# sls_v1_0.net
KiCad netlist of a schematic drawn in EAGLE
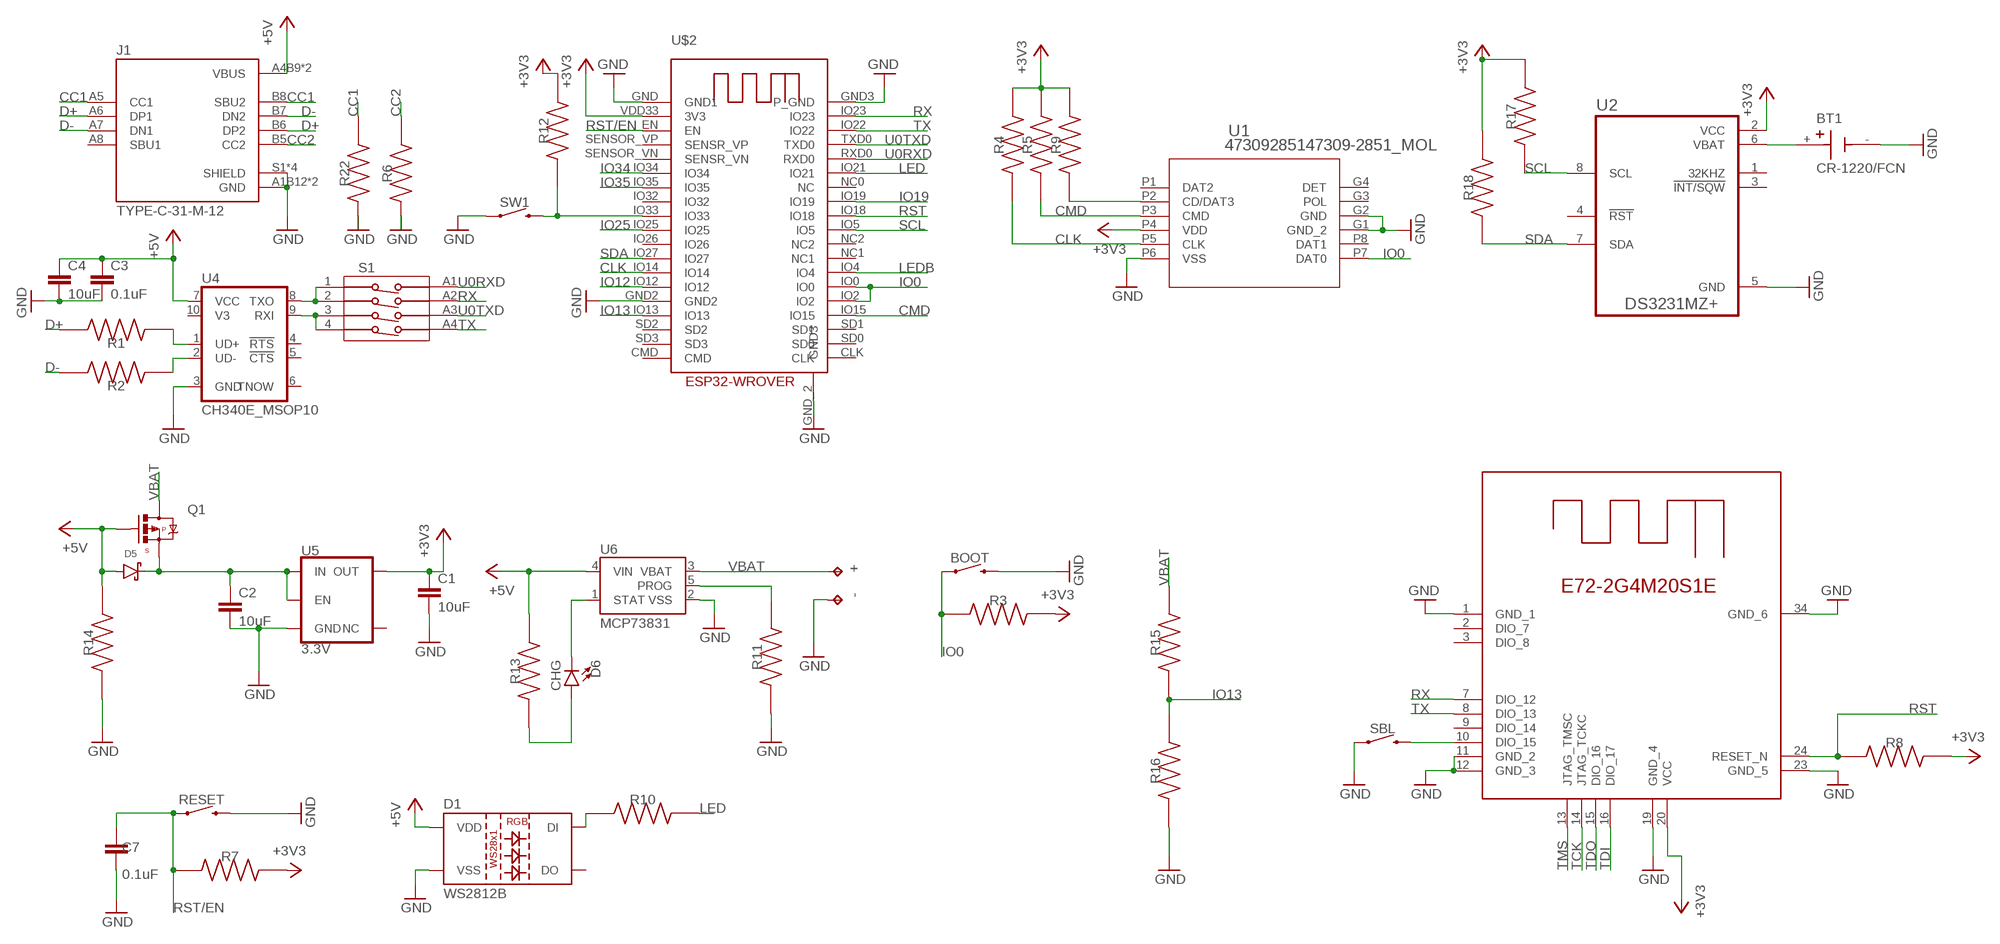
[diagram p0: schematic, sheet 1]

(export (version "E")
  (design (tool "Eeschema 10.0.6"))
  (components
    (comp (ref "+")
      (value "TPTP14R")
      (footprint "eagle-import:TP14R")
      (libsource (lib "eagle-import") (part "TPTP14R"))
    )
    (comp (ref "-")
      (value "TPTP14R")
      (footprint "eagle-import:TP14R")
      (libsource (lib "eagle-import") (part "TPTP14R"))
    )
    (comp (ref "BOOT")
      (value "MOMENTARY-SWITCH-SPST-SMD-4.6X2.8MM")
      (footprint "eagle-import:TACTILE_SWITCH_SMD_4.6X2.8MM")
      (libsource (lib "eagle-import") (part "MOMENTARY-SWITCH-SPST-SMD-4.6X2.8MM"))
    )
    (comp (ref "BT1")
      (value "CR-1220/FCN")
      (footprint "eagle-import:BAT_CR-1220_FCN")
      (fields (field (name "MF") "Panasonic -"))
      (libsource (lib "eagle-import") (part "CR-1220/FCN"))
    )
    (comp (ref "C1")
      (value "10uF")
      (footprint "eagle-import:0805")
      (libsource (lib "eagle-import") (part "10UF-0805-10V-10%"))
    )
    (comp (ref "C2")
      (value "10uF")
      (footprint "eagle-import:0805")
      (libsource (lib "eagle-import") (part "10UF-0805-10V-10%"))
    )
    (comp (ref "C3")
      (value "0.1uF")
      (footprint "eagle-import:0603")
      (libsource (lib "eagle-import") (part "0.1UF-0603-25V-(+80/-20%)"))
    )
    (comp (ref "C4")
      (value "10uF")
      (footprint "eagle-import:0603")
      (libsource (lib "eagle-import") (part "10UF-0603-6.3V-20%"))
    )
    (comp (ref "C7")
      (value "0.1uF")
      (footprint "eagle-import:0603")
      (libsource (lib "eagle-import") (part "0.1UF-0603-25V-5%"))
    )
    (comp (ref "D1")
      (value "WS2812B")
      (footprint "eagle-import:WS2812B")
      (libsource (lib "eagle-import") (part "WS2812B"))
    )
    (comp (ref "D5")
      (value "DIODE-SCHOTTKY")
      (footprint "eagle-import:SOD-323")
      (libsource (lib "eagle-import") (part "DIODE-SCHOTTKY"))
    )
    (comp (ref "D6")
      (value "CHG")
      (footprint "eagle-import:LED-0603")
      (libsource (lib "eagle-import") (part "LED-BLUE0603"))
    )
    (comp (ref "J1")
      (value "TYPE-C-31-M-12")
      (footprint "eagle-import:HRO_TYPE-C-31-M-12")
      (fields (field (name "MF") "HRO Electronics Co., Ltd."))
      (libsource (lib "eagle-import") (part "TYPE-C-31-M-12"))
    )
    (comp (ref "Q1")
      (value "MOSFET-PCHANNEL")
      (footprint "eagle-import:SOT23")
      (libsource (lib "eagle-import") (part "MOSFET-PCHANNEL"))
    )
    (comp (ref "R1")
      (value "RC0402FR-073M6L")
      (footprint "eagle-import:RESC1005X40N")
      (fields (field (name "MF") "Yageo"))
      (libsource (lib "eagle-import") (part "RC0402FR-073M6L"))
    )
    (comp (ref "R2")
      (value "RC0402FR-073M6L")
      (footprint "eagle-import:RESC1005X40N")
      (fields (field (name "MF") "Yageo"))
      (libsource (lib "eagle-import") (part "RC0402FR-073M6L"))
    )
    (comp (ref "R3")
      (value "RC0402FR-073M6L")
      (footprint "eagle-import:RESC1005X40N")
      (fields (field (name "MF") "Yageo"))
      (libsource (lib "eagle-import") (part "RC0402FR-073M6L"))
    )
    (comp (ref "R4")
      (value "RC0402FR-073M6L")
      (footprint "eagle-import:RESC1005X40N")
      (fields (field (name "MF") "Yageo"))
      (libsource (lib "eagle-import") (part "RC0402FR-073M6L"))
    )
    (comp (ref "R5")
      (value "RC0402FR-073M6L")
      (footprint "eagle-import:RESC1005X40N")
      (fields (field (name "MF") "Yageo"))
      (libsource (lib "eagle-import") (part "RC0402FR-073M6L"))
    )
    (comp (ref "R6")
      (value "5.1k")
      (footprint "eagle-import:RESC1005X40N")
      (fields (field (name "MF") "Yageo") (field (name "MP") "RC0402FR-073M6L"))
      (libsource (lib "eagle-import") (part "RC0402FR-073M6L"))
    )
    (comp (ref "R7")
      (value "RC0402FR-073M6L")
      (footprint "eagle-import:RESC1005X40N")
      (fields (field (name "MF") "Yageo"))
      (libsource (lib "eagle-import") (part "RC0402FR-073M6L"))
    )
    (comp (ref "R8")
      (value "100k")
      (footprint "eagle-import:RESC1005X40N")
      (fields (field (name "MF") "Yageo") (field (name "MP") "RC0402FR-073M6L"))
      (libsource (lib "eagle-import") (part "RC0402FR-073M6L"))
    )
    (comp (ref "R9")
      (value "RC0402FR-073M6L")
      (footprint "eagle-import:RESC1005X40N")
      (fields (field (name "MF") "Yageo"))
      (libsource (lib "eagle-import") (part "RC0402FR-073M6L"))
    )
    (comp (ref "R10")
      (value "RC0402FR-073M6L")
      (footprint "eagle-import:RESC1005X40N")
      (fields (field (name "MF") "Yageo"))
      (libsource (lib "eagle-import") (part "RC0402FR-073M6L"))
    )
    (comp (ref "R11")
      (value "2.7k")
      (footprint "eagle-import:RESC1005X40N")
      (fields (field (name "MF") "Yageo") (field (name "MP") "RC0402FR-073M6L"))
      (libsource (lib "eagle-import") (part "RC0402FR-073M6L"))
    )
    (comp (ref "R12")
      (value "RC0402FR-073M6L")
      (footprint "eagle-import:RESC1005X40N")
      (fields (field (name "MF") "Yageo"))
      (libsource (lib "eagle-import") (part "RC0402FR-073M6L"))
    )
    (comp (ref "R13")
      (value "RC0402FR-073M6L")
      (footprint "eagle-import:RESC1005X40N")
      (fields (field (name "MF") "Yageo"))
      (libsource (lib "eagle-import") (part "RC0402FR-073M6L"))
    )
    (comp (ref "R14")
      (value "RC0402FR-073M6L")
      (footprint "eagle-import:RESC1005X40N")
      (fields (field (name "MF") "Yageo"))
      (libsource (lib "eagle-import") (part "RC0402FR-073M6L"))
    )
    (comp (ref "R15")
      (value "RC0402FR-073M6L")
      (footprint "eagle-import:RESC1005X40N")
      (fields (field (name "MF") "Yageo"))
      (libsource (lib "eagle-import") (part "RC0402FR-073M6L"))
    )
    (comp (ref "R16")
      (value "RC0402FR-073M6L")
      (footprint "eagle-import:RESC1005X40N")
      (fields (field (name "MF") "Yageo"))
      (libsource (lib "eagle-import") (part "RC0402FR-073M6L"))
    )
    (comp (ref "R17")
      (value "RC0402FR-073M6L")
      (footprint "eagle-import:RESC1005X40N")
      (fields (field (name "MF") "Yageo"))
      (libsource (lib "eagle-import") (part "RC0402FR-073M6L"))
    )
    (comp (ref "R18")
      (value "RC0402FR-073M6L")
      (footprint "eagle-import:RESC1005X40N")
      (fields (field (name "MF") "Yageo"))
      (libsource (lib "eagle-import") (part "RC0402FR-073M6L"))
    )
    (comp (ref "R22")
      (value "5.1k")
      (footprint "eagle-import:RESC1005X40N")
      (fields (field (name "MF") "Yageo") (field (name "MP") "RC0402FR-073M6L"))
      (libsource (lib "eagle-import") (part "RC0402FR-073M6L"))
    )
    (comp (ref "RESET")
      (value "MOMENTARY-SWITCH-SPST-SMD-4.6X2.8MM")
      (footprint "eagle-import:TACTILE_SWITCH_SMD_4.6X2.8MM")
      (libsource (lib "eagle-import") (part "MOMENTARY-SWITCH-SPST-SMD-4.6X2.8MM"))
    )
    (comp (ref "S1")
      (value "416131160804")
      (footprint "eagle-import:416131160804")
      (fields (field (name "MF") "Wurth Elektronik"))
      (libsource (lib "eagle-import") (part "416131160804"))
    )
    (comp (ref "SBL")
      (value "MOMENTARY-SWITCH-SPST-SMD-4.6X2.8MM")
      (footprint "eagle-import:TACTILE_SWITCH_SMD_4.6X2.8MM")
      (libsource (lib "eagle-import") (part "MOMENTARY-SWITCH-SPST-SMD-4.6X2.8MM"))
    )
    (comp (ref "SW1")
      (value "MOMENTARY-SWITCH-SPST-SMD-4.6X2.8MM")
      (footprint "eagle-import:TACTILE_SWITCH_SMD_4.6X2.8MM")
      (libsource (lib "eagle-import") (part "MOMENTARY-SWITCH-SPST-SMD-4.6X2.8MM"))
    )
    (comp (ref "U$1")
      (value "E72-2G4M20S1E")
      (footprint "eagle-import:E72-2G4M20S1E")
      (libsource (lib "eagle-import") (part "E72-2G4M20S1E"))
    )
    (comp (ref "U$2")
      (value "ESP32-WROVER")
      (footprint "eagle-import:ESP32-WROVER")
      (libsource (lib "eagle-import") (part "ESP32-WROVER"))
    )
    (comp (ref "U1")
      (value "47309285147309-2851_MOL")
      (footprint "eagle-import:47309-2851_MOL")
      (fields
        (field (name "MANUFACTURER_PART_NUMBER") "473092851")
        (field (name "COPYRIGHT") "Copyright (C) 2021 Ultra Librarian. All rights reserved.")
      )
      (libsource (lib "eagle-import") (part "47309285147309-2851_MOL"))
    )
    (comp (ref "U2")
      (value "DS3231MZ+")
      (footprint "eagle-import:SOIC127P600X175-8N")
      (fields (field (name "MF") "Maxim Integrated"))
      (libsource (lib "eagle-import") (part "DS3231MZ+"))
    )
    (comp (ref "U4")
      (value "CH340E_MSOP10")
      (footprint "eagle-import:MSOP10")
      (fields (field (name "MF") "WCH") (field (name "MP") "CH340E"))
      (libsource (lib "eagle-import") (part "CH340E_MSOP10"))
    )
    (comp (ref "U5")
      (value "3.3V")
      (footprint "eagle-import:SOT23-5")
      (libsource (lib "eagle-import") (part "V_REG_AP2112K-3.3V"))
    )
    (comp (ref "U6")
      (value "MCP73831")
      (footprint "eagle-import:SOT23-5")
      (libsource (lib "eagle-import") (part "MCP73831"))
    )
  )
  (nets
    (net (code "1") (name "+3V3") (class "Default")
      (node (ref "C1") (pin "1") (pinfunction "1_1") (pintype "passive"))
      (node (ref "R12") (pin "2") (pinfunction "2_2") (pintype "passive"))
      (node (ref "R17") (pin "2") (pinfunction "2_2") (pintype "passive"))
      (node (ref "R18") (pin "2") (pinfunction "2_2") (pintype "passive"))
      (node (ref "R3") (pin "2") (pinfunction "2_2") (pintype "passive"))
      (node (ref "R4") (pin "2") (pinfunction "2_2") (pintype "passive"))
      (node (ref "R5") (pin "2") (pinfunction "2_2") (pintype "passive"))
      (node (ref "R7") (pin "2") (pinfunction "2_2") (pintype "passive"))
      (node (ref "R8") (pin "2") (pinfunction "2_2") (pintype "passive"))
      (node (ref "R9") (pin "2") (pinfunction "2_2") (pintype "passive"))
      (node (ref "U$1") (pin "20") (pinfunction "VCC_20") (pintype "bidirectional"))
      (node (ref "U$2") (pin "VDD33") (pinfunction "3V3_VDD33") (pintype "bidirectional"))
      (node (ref "U1") (pin "P4") (pinfunction "VDD_P4") (pintype "power_in"))
      (node (ref "U2") (pin "2") (pinfunction "VCC_2") (pintype "power_in"))
      (node (ref "U5") (pin "5") (pinfunction "OUT_5") (pintype "passive"))
    )
    (net (code "2") (name "+5V") (class "Default")
      (node (ref "C3") (pin "1") (pinfunction "1_1") (pintype "passive"))
      (node (ref "C4") (pin "1") (pinfunction "1_1") (pintype "passive"))
      (node (ref "D1") (pin "1") (pinfunction "VDD_1") (pintype "bidirectional"))
      (node (ref "D5") (pin "A") (pinfunction "A_A") (pintype "passive"))
      (node (ref "J1") (pin "A4B9") (pinfunction "VBUS_A4B9") (pintype "power_in"))
      (node (ref "J1") (pin "B4A9") (pinfunction "VBUS_B4A9") (pintype "power_in"))
      (node (ref "Q1") (pin "1") (pinfunction "G_1") (pintype "passive"))
      (node (ref "R13") (pin "2") (pinfunction "2_2") (pintype "passive"))
      (node (ref "R14") (pin "2") (pinfunction "2_2") (pintype "passive"))
      (node (ref "U4") (pin "7") (pinfunction "VCC_7") (pintype "bidirectional"))
      (node (ref "U6") (pin "4") (pinfunction "VIN_4") (pintype "power_in"))
    )
    (net (code "3") (name "/CC1") (class "Default")
      (node (ref "J1") (pin "A5") (pinfunction "CC1_A5") (pintype "bidirectional"))
      (node (ref "J1") (pin "B8") (pinfunction "SBU2_B8") (pintype "bidirectional"))
      (node (ref "R22") (pin "2") (pinfunction "2_2") (pintype "passive"))
    )
    (net (code "4") (name "/CC2") (class "Default")
      (node (ref "J1") (pin "B5") (pinfunction "CC2_B5") (pintype "bidirectional"))
      (node (ref "R6") (pin "2") (pinfunction "2_2") (pintype "passive"))
    )
    (net (code "5") (name "/CLK") (class "Default")
      (node (ref "R4") (pin "1") (pinfunction "1_1") (pintype "passive"))
      (node (ref "U$2") (pin "IO14") (pinfunction "IO14_IO14") (pintype "bidirectional"))
      (node (ref "U1") (pin "P5") (pinfunction "CLK_P5") (pintype "passive"))
    )
    (net (code "6") (name "/CMD") (class "Default")
      (node (ref "R5") (pin "1") (pinfunction "1_1") (pintype "passive"))
      (node (ref "U$2") (pin "IO15") (pinfunction "IO15_IO15") (pintype "bidirectional"))
      (node (ref "U1") (pin "P3") (pinfunction "CMD_P3") (pintype "passive"))
    )
    (net (code "7") (name "/D+") (class "Default")
      (node (ref "J1") (pin "A6") (pinfunction "DP1_A6") (pintype "bidirectional"))
      (node (ref "J1") (pin "B6") (pinfunction "DP2_B6") (pintype "bidirectional"))
      (node (ref "R1") (pin "2") (pinfunction "2_2") (pintype "passive"))
    )
    (net (code "8") (name "/D-") (class "Default")
      (node (ref "J1") (pin "A7") (pinfunction "DN1_A7") (pintype "bidirectional"))
      (node (ref "J1") (pin "B7") (pinfunction "DN2_B7") (pintype "bidirectional"))
      (node (ref "R2") (pin "2") (pinfunction "2_2") (pintype "passive"))
    )
    (net (code "9") (name "/IO0") (class "Default")
      (node (ref "BOOT") (pin "1") (pinfunction "1_1") (pintype "passive"))
      (node (ref "BOOT") (pin "2") (pinfunction "1_2") (pintype "passive"))
      (node (ref "R3") (pin "1") (pinfunction "1_1") (pintype "passive"))
      (node (ref "U$2") (pin "IO0") (pinfunction "IO0_IO0") (pintype "bidirectional"))
      (node (ref "U$2") (pin "IO2") (pinfunction "IO2_IO2") (pintype "bidirectional"))
      (node (ref "U1") (pin "P7") (pinfunction "DAT0_P7") (pintype "bidirectional"))
    )
    (net (code "10") (name "/IO12") (class "Default")
      (node (ref "U$2") (pin "IO12") (pinfunction "IO12_IO12") (pintype "bidirectional"))
    )
    (net (code "11") (name "/IO13") (class "Default")
      (node (ref "R15") (pin "1") (pinfunction "1_1") (pintype "passive"))
      (node (ref "R16") (pin "2") (pinfunction "2_2") (pintype "passive"))
      (node (ref "U$2") (pin "IO13") (pinfunction "IO13_IO13") (pintype "bidirectional"))
    )
    (net (code "12") (name "/IO19") (class "Default")
      (node (ref "U$2") (pin "IO19") (pinfunction "IO19_IO19") (pintype "bidirectional"))
    )
    (net (code "13") (name "/IO25") (class "Default")
      (node (ref "U$2") (pin "IO25") (pinfunction "IO25_IO25") (pintype "bidirectional"))
    )
    (net (code "14") (name "/IO34") (class "Default")
      (node (ref "U$2") (pin "IO34") (pinfunction "IO34_IO34") (pintype "bidirectional"))
    )
    (net (code "15") (name "/IO35") (class "Default")
      (node (ref "U$2") (pin "IO35") (pinfunction "IO35_IO35") (pintype "bidirectional"))
    )
    (net (code "16") (name "/LED") (class "Default")
      (node (ref "R10") (pin "2") (pinfunction "2_2") (pintype "passive"))
      (node (ref "U$2") (pin "IO21") (pinfunction "IO21_IO21") (pintype "bidirectional"))
    )
    (net (code "17") (name "/LEDB") (class "Default")
      (node (ref "U$2") (pin "IO4") (pinfunction "IO4_IO4") (pintype "bidirectional"))
    )
    (net (code "18") (name "/RST") (class "Default")
      (node (ref "R8") (pin "1") (pinfunction "1_1") (pintype "passive"))
      (node (ref "U$1") (pin "24") (pinfunction "RESET_N_24") (pintype "bidirectional"))
      (node (ref "U$2") (pin "IO18") (pinfunction "IO18_IO18") (pintype "bidirectional"))
    )
    (net (code "19") (name "/RST{slash}EN") (class "Default")
      (node (ref "C7") (pin "1") (pinfunction "1_1") (pintype "passive"))
      (node (ref "R7") (pin "1") (pinfunction "1_1") (pintype "passive"))
      (node (ref "RESET") (pin "1") (pinfunction "1_1") (pintype "passive"))
      (node (ref "RESET") (pin "2") (pinfunction "1_2") (pintype "passive"))
      (node (ref "U$2") (pin "EN") (pinfunction "EN_EN") (pintype "bidirectional"))
    )
    (net (code "20") (name "/RX") (class "Default")
      (node (ref "S1") (pin "A2") (pinfunction "A2_A2") (pintype "passive"))
      (node (ref "U$1") (pin "7") (pinfunction "DIO_12_7") (pintype "bidirectional"))
      (node (ref "U$2") (pin "IO23") (pinfunction "IO23_IO23") (pintype "bidirectional"))
    )
    (net (code "21") (name "/SCL") (class "Default")
      (node (ref "R17") (pin "1") (pinfunction "1_1") (pintype "passive"))
      (node (ref "U$2") (pin "IO5") (pinfunction "IO5_IO5") (pintype "bidirectional"))
      (node (ref "U2") (pin "8") (pinfunction "SCL_8") (pintype "input"))
    )
    (net (code "22") (name "/SDA") (class "Default")
      (node (ref "R18") (pin "1") (pinfunction "1_1") (pintype "passive"))
      (node (ref "U$2") (pin "IO27") (pinfunction "IO27_IO27") (pintype "bidirectional"))
      (node (ref "U2") (pin "7") (pinfunction "SDA_7") (pintype "bidirectional"))
    )
    (net (code "23") (name "/TCK") (class "Default")
      (node (ref "U$1") (pin "14") (pinfunction "JTAG_TCKC_14") (pintype "bidirectional"))
    )
    (net (code "24") (name "/TDI") (class "Default")
      (node (ref "U$1") (pin "16") (pinfunction "DIO_17_16") (pintype "bidirectional"))
    )
    (net (code "25") (name "/TDO") (class "Default")
      (node (ref "U$1") (pin "15") (pinfunction "DIO_16_15") (pintype "bidirectional"))
    )
    (net (code "26") (name "/TMS") (class "Default")
      (node (ref "U$1") (pin "13") (pinfunction "JTAG_TMSC_13") (pintype "bidirectional"))
    )
    (net (code "27") (name "/TX") (class "Default")
      (node (ref "S1") (pin "A4") (pinfunction "A4_A4") (pintype "passive"))
      (node (ref "U$1") (pin "8") (pinfunction "DIO_13_8") (pintype "bidirectional"))
      (node (ref "U$2") (pin "IO22") (pinfunction "IO22_IO22") (pintype "bidirectional"))
    )
    (net (code "28") (name "/U0RXD") (class "Default")
      (node (ref "S1") (pin "A1") (pinfunction "A1_A1") (pintype "passive"))
      (node (ref "U$2") (pin "RXD0") (pinfunction "RXD0_RXD0") (pintype "bidirectional"))
    )
    (net (code "29") (name "/U0TXD") (class "Default")
      (node (ref "S1") (pin "A3") (pinfunction "A3_A3") (pintype "passive"))
      (node (ref "U$2") (pin "TXD0") (pinfunction "TXD0_TXD0") (pintype "bidirectional"))
    )
    (net (code "30") (name "/VBAT") (class "Default")
      (node (ref "+") (pin "TP") (pinfunction "TP_TP") (pintype "input"))
      (node (ref "Q1") (pin "3") (pinfunction "D_3") (pintype "passive"))
      (node (ref "R15") (pin "2") (pinfunction "2_2") (pintype "passive"))
      (node (ref "U6") (pin "3") (pinfunction "VBAT_3") (pintype "power_in"))
    )
    (net (code "31") (name "GND") (class "Default")
      (node (ref "-") (pin "TP") (pinfunction "TP_TP") (pintype "input"))
      (node (ref "BOOT") (pin "3") (pinfunction "2_3") (pintype "passive"))
      (node (ref "BOOT") (pin "4") (pinfunction "2_4") (pintype "passive"))
      (node (ref "BT1") (pin "-") (pinfunction "-_-") (pintype "passive"))
      (node (ref "C1") (pin "2") (pinfunction "2_2") (pintype "passive"))
      (node (ref "C2") (pin "2") (pinfunction "2_2") (pintype "passive"))
      (node (ref "C3") (pin "2") (pinfunction "2_2") (pintype "passive"))
      (node (ref "C4") (pin "2") (pinfunction "2_2") (pintype "passive"))
      (node (ref "C7") (pin "2") (pinfunction "2_2") (pintype "passive"))
      (node (ref "D1") (pin "3") (pinfunction "VSS_3") (pintype "bidirectional"))
      (node (ref "J1") (pin "A1B12") (pinfunction "GND_A1B12") (pintype "power_in"))
      (node (ref "J1") (pin "B1A12") (pinfunction "GND_B1A12") (pintype "power_in"))
      (node (ref "J1") (pin "S1") (pinfunction "SHIELD_S1") (pintype "passive"))
      (node (ref "J1") (pin "S2") (pinfunction "SHIELD_S2") (pintype "passive"))
      (node (ref "J1") (pin "S3") (pinfunction "SHIELD_S3") (pintype "passive"))
      (node (ref "J1") (pin "S4") (pinfunction "SHIELD_S4") (pintype "passive"))
      (node (ref "R11") (pin "1") (pinfunction "1_1") (pintype "passive"))
      (node (ref "R14") (pin "1") (pinfunction "1_1") (pintype "passive"))
      (node (ref "R16") (pin "1") (pinfunction "1_1") (pintype "passive"))
      (node (ref "R22") (pin "1") (pinfunction "1_1") (pintype "passive"))
      (node (ref "R6") (pin "1") (pinfunction "1_1") (pintype "passive"))
      (node (ref "RESET") (pin "3") (pinfunction "2_3") (pintype "passive"))
      (node (ref "RESET") (pin "4") (pinfunction "2_4") (pintype "passive"))
      (node (ref "SBL") (pin "1") (pinfunction "1_1") (pintype "passive"))
      (node (ref "SBL") (pin "2") (pinfunction "1_2") (pintype "passive"))
      (node (ref "SW1") (pin "1") (pinfunction "1_1") (pintype "passive"))
      (node (ref "SW1") (pin "2") (pinfunction "1_2") (pintype "passive"))
      (node (ref "U$1") (pin "1") (pinfunction "GND_1_1") (pintype "bidirectional"))
      (node (ref "U$1") (pin "11") (pinfunction "GND_2_11") (pintype "bidirectional"))
      (node (ref "U$1") (pin "12") (pinfunction "GND_3_12") (pintype "bidirectional"))
      (node (ref "U$1") (pin "19") (pinfunction "GND_4_19") (pintype "bidirectional"))
      (node (ref "U$1") (pin "23") (pinfunction "GND_5_23") (pintype "bidirectional"))
      (node (ref "U$1") (pin "34") (pinfunction "GND_6_34") (pintype "bidirectional"))
      (node (ref "U$2") (pin "GND") (pinfunction "GND1_GND") (pintype "bidirectional"))
      (node (ref "U$2") (pin "GND2") (pinfunction "GND2_GND2") (pintype "bidirectional"))
      (node (ref "U$2") (pin "GND3") (pinfunction "P_GND_GND3") (pintype "bidirectional"))
      (node (ref "U$2") (pin "GND_2") (pinfunction "GND3_GND_2") (pintype "bidirectional"))
      (node (ref "U1") (pin "G1") (pinfunction "GND_2_G1") (pintype "passive"))
      (node (ref "U1") (pin "G2") (pinfunction "GND_G2") (pintype "passive"))
      (node (ref "U1") (pin "P6") (pinfunction "VSS_P6") (pintype "passive"))
      (node (ref "U2") (pin "5") (pinfunction "GND_5") (pintype "power_in"))
      (node (ref "U4") (pin "3") (pinfunction "GND_3") (pintype "bidirectional"))
      (node (ref "U5") (pin "2") (pinfunction "GND_2") (pintype "input"))
      (node (ref "U6") (pin "2") (pinfunction "VSS_2") (pintype "power_in"))
    )
    (net (code "32") (name "Net-(D1-DI)") (class "Default")
      (node (ref "D1") (pin "4") (pinfunction "DI_4") (pintype "bidirectional"))
      (node (ref "R10") (pin "1") (pinfunction "1_1") (pintype "passive"))
    )
    (net (code "33") (name "Net-(D6-PadA)") (class "Default")
      (node (ref "D6") (pin "A") (pinfunction "A_A") (pintype "passive"))
      (node (ref "R13") (pin "1") (pinfunction "1_1") (pintype "passive"))
    )
    (net (code "34") (name "Net-(Q1-S)") (class "Default")
      (node (ref "C2") (pin "1") (pinfunction "1_1") (pintype "passive"))
      (node (ref "D5") (pin "C") (pinfunction "C_C") (pintype "passive"))
      (node (ref "Q1") (pin "2") (pinfunction "S_2") (pintype "passive"))
      (node (ref "U5") (pin "1") (pinfunction "IN_1") (pintype "input"))
      (node (ref "U5") (pin "3") (pinfunction "EN_3") (pintype "input"))
    )
    (net (code "35") (name "Net-(R12-Pad1)") (class "Default")
      (node (ref "R12") (pin "1") (pinfunction "1_1") (pintype "passive"))
      (node (ref "SW1") (pin "3") (pinfunction "2_3") (pintype "passive"))
      (node (ref "SW1") (pin "4") (pinfunction "2_4") (pintype "passive"))
      (node (ref "U$2") (pin "IO33") (pinfunction "IO33_IO33") (pintype "bidirectional"))
    )
    (net (code "36") (name "Net-(U$1-DIO_15)") (class "Default")
      (node (ref "SBL") (pin "3") (pinfunction "2_3") (pintype "passive"))
      (node (ref "SBL") (pin "4") (pinfunction "2_4") (pintype "passive"))
      (node (ref "U$1") (pin "10") (pinfunction "DIO_15_10") (pintype "bidirectional"))
    )
    (net (code "37") (name "Net-(U1-CD{slash}DAT3)") (class "Default")
      (node (ref "R9") (pin "1") (pinfunction "1_1") (pintype "passive"))
      (node (ref "U1") (pin "P2") (pinfunction "CD/DAT3_P2") (pintype "passive"))
    )
    (net (code "38") (name "Net-(U2-VBAT)") (class "Default")
      (node (ref "BT1") (pin "+") (pinfunction "+_+") (pintype "passive"))
      (node (ref "U2") (pin "6") (pinfunction "VBAT_6") (pintype "power_in"))
    )
    (net (code "39") (name "Net-(U4-RXI)") (class "Default")
      (node (ref "S1") (pin "3") (pinfunction "3_3") (pintype "passive"))
      (node (ref "S1") (pin "4") (pinfunction "4_4") (pintype "passive"))
      (node (ref "U4") (pin "9") (pinfunction "RXI_9") (pintype "bidirectional"))
    )
    (net (code "40") (name "Net-(U4-TXO)") (class "Default")
      (node (ref "S1") (pin "1") (pinfunction "1_1") (pintype "passive"))
      (node (ref "S1") (pin "2") (pinfunction "2_2") (pintype "passive"))
      (node (ref "U4") (pin "8") (pinfunction "TXO_8") (pintype "bidirectional"))
    )
    (net (code "41") (name "Net-(U4-UD+)") (class "Default")
      (node (ref "R1") (pin "1") (pinfunction "1_1") (pintype "passive"))
      (node (ref "U4") (pin "1") (pinfunction "UD+_1") (pintype "bidirectional"))
    )
    (net (code "42") (name "Net-(U4-UD-)") (class "Default")
      (node (ref "R2") (pin "1") (pinfunction "1_1") (pintype "passive"))
      (node (ref "U4") (pin "2") (pinfunction "UD-_2") (pintype "bidirectional"))
    )
    (net (code "43") (name "Net-(U6-PROG)") (class "Default")
      (node (ref "R11") (pin "2") (pinfunction "2_2") (pintype "passive"))
      (node (ref "U6") (pin "5") (pinfunction "PROG_5") (pintype "input"))
    )
    (net (code "44") (name "Net-(U6-STAT)") (class "Default")
      (node (ref "D6") (pin "C") (pinfunction "C_C") (pintype "passive"))
      (node (ref "U6") (pin "1") (pinfunction "STAT_1") (pintype "output"))
    )
    (net (code "45") (name "unconnected-(D1-DO-Pad2)") (class "Default")
      (node (ref "D1") (pin "2") (pinfunction "DO_2") (pintype "bidirectional"))
    )
    (net (code "46") (name "unconnected-(J1-SBU1-PadA8)") (class "Default")
      (node (ref "J1") (pin "A8") (pinfunction "SBU1_A8") (pintype "bidirectional"))
    )
    (net (code "47") (name "unconnected-(U$1-DIO_7-Pad2)") (class "Default")
      (node (ref "U$1") (pin "2") (pinfunction "DIO_7_2") (pintype "bidirectional"))
    )
    (net (code "48") (name "unconnected-(U$1-DIO_8-Pad3)") (class "Default")
      (node (ref "U$1") (pin "3") (pinfunction "DIO_8_3") (pintype "bidirectional"))
    )
    (net (code "49") (name "unconnected-(U$1-DIO_14-Pad9)") (class "Default")
      (node (ref "U$1") (pin "9") (pinfunction "DIO_14_9") (pintype "bidirectional"))
    )
    (net (code "50") (name "unconnected-(U$2-NC-PadNC0)") (class "Default")
      (node (ref "U$2") (pin "NC0") (pinfunction "NC_NC0") (pintype "bidirectional"))
    )
    (net (code "51") (name "unconnected-(U$2-PadCLK)") (class "Default")
      (node (ref "U$2") (pin "CLK") (pinfunction "CLK_CLK") (pintype "bidirectional"))
    )
    (net (code "52") (name "unconnected-(U$2-PadCMD)") (class "Default")
      (node (ref "U$2") (pin "CMD") (pinfunction "CMD_CMD") (pintype "bidirectional"))
    )
    (net (code "53") (name "unconnected-(U$2-PadIO26)") (class "Default")
      (node (ref "U$2") (pin "IO26") (pinfunction "IO26_IO26") (pintype "bidirectional"))
    )
    (net (code "54") (name "unconnected-(U$2-PadIO32)") (class "Default")
      (node (ref "U$2") (pin "IO32") (pinfunction "IO32_IO32") (pintype "bidirectional"))
    )
    (net (code "55") (name "unconnected-(U$2-PadNC1)") (class "Default")
      (node (ref "U$2") (pin "NC1") (pinfunction "NC1_NC1") (pintype "bidirectional"))
    )
    (net (code "56") (name "unconnected-(U$2-PadNC2)") (class "Default")
      (node (ref "U$2") (pin "NC2") (pinfunction "NC2_NC2") (pintype "bidirectional"))
    )
    (net (code "57") (name "unconnected-(U$2-PadSD0)") (class "Default")
      (node (ref "U$2") (pin "SD0") (pinfunction "SD0_SD0") (pintype "bidirectional"))
    )
    (net (code "58") (name "unconnected-(U$2-PadSD1)") (class "Default")
      (node (ref "U$2") (pin "SD1") (pinfunction "SD1_SD1") (pintype "bidirectional"))
    )
    (net (code "59") (name "unconnected-(U$2-PadSD2)") (class "Default")
      (node (ref "U$2") (pin "SD2") (pinfunction "SD2_SD2") (pintype "bidirectional"))
    )
    (net (code "60") (name "unconnected-(U$2-PadSD3)") (class "Default")
      (node (ref "U$2") (pin "SD3") (pinfunction "SD3_SD3") (pintype "bidirectional"))
    )
    (net (code "61") (name "unconnected-(U$2-SENSR_VN-PadSENSOR_VN)") (class "Default")
      (node (ref "U$2") (pin "SENSOR_VN") (pinfunction "SENSR_VN_SENSOR_VN") (pintype "bidirectional"))
    )
    (net (code "62") (name "unconnected-(U$2-SENSR_VP-PadSENSOR_VP)") (class "Default")
      (node (ref "U$2") (pin "SENSOR_VP") (pinfunction "SENSR_VP_SENSOR_VP") (pintype "bidirectional"))
    )
    (net (code "63") (name "unconnected-(U1-DAT1-PadP8)") (class "Default")
      (node (ref "U1") (pin "P8") (pinfunction "DAT1_P8") (pintype "bidirectional"))
    )
    (net (code "64") (name "unconnected-(U1-DAT2-PadP1)") (class "Default")
      (node (ref "U1") (pin "P1") (pinfunction "DAT2_P1") (pintype "bidirectional"))
    )
    (net (code "65") (name "unconnected-(U1-DET-PadG4)") (class "Default")
      (node (ref "U1") (pin "G4") (pinfunction "DET_G4") (pintype "passive"))
    )
    (net (code "66") (name "unconnected-(U1-POL-PadG3)") (class "Default")
      (node (ref "U1") (pin "G3") (pinfunction "POL_G3") (pintype "passive"))
    )
    (net (code "67") (name "unconnected-(U2-32KHZ-Pad1)") (class "Default")
      (node (ref "U2") (pin "1") (pinfunction "32KHZ_1") (pintype "output"))
    )
    (net (code "68") (name "unconnected-(U2-~{INT{slash}SQW}-Pad3)") (class "Default")
      (node (ref "U2") (pin "3") (pinfunction "~{INT/SQW}_3") (pintype "output"))
    )
    (net (code "69") (name "unconnected-(U2-~{RST}-Pad4)") (class "Default")
      (node (ref "U2") (pin "4") (pinfunction "~{RST}_4") (pintype "bidirectional"))
    )
    (net (code "70") (name "unconnected-(U4-TNOW-Pad6)") (class "Default")
      (node (ref "U4") (pin "6") (pinfunction "TNOW_6") (pintype "bidirectional"))
    )
    (net (code "71") (name "unconnected-(U4-V3-Pad10)") (class "Default")
      (node (ref "U4") (pin "10") (pinfunction "V3_10") (pintype "bidirectional"))
    )
    (net (code "72") (name "unconnected-(U4-~{CTS}-Pad5)") (class "Default")
      (node (ref "U4") (pin "5") (pinfunction "~{CTS}_5") (pintype "bidirectional"))
    )
    (net (code "73") (name "unconnected-(U4-~{RTS}-Pad4)") (class "Default")
      (node (ref "U4") (pin "4") (pinfunction "~{RTS}_4") (pintype "bidirectional"))
    )
    (net (code "74") (name "unconnected-(U5-NC-Pad4)") (class "Default")
      (node (ref "U5") (pin "4") (pinfunction "NC_4") (pintype "no_connect"))
    )
  )
)
